# final_rev_no_smd.net
KiCad netlist of a schematic drawn in EAGLE
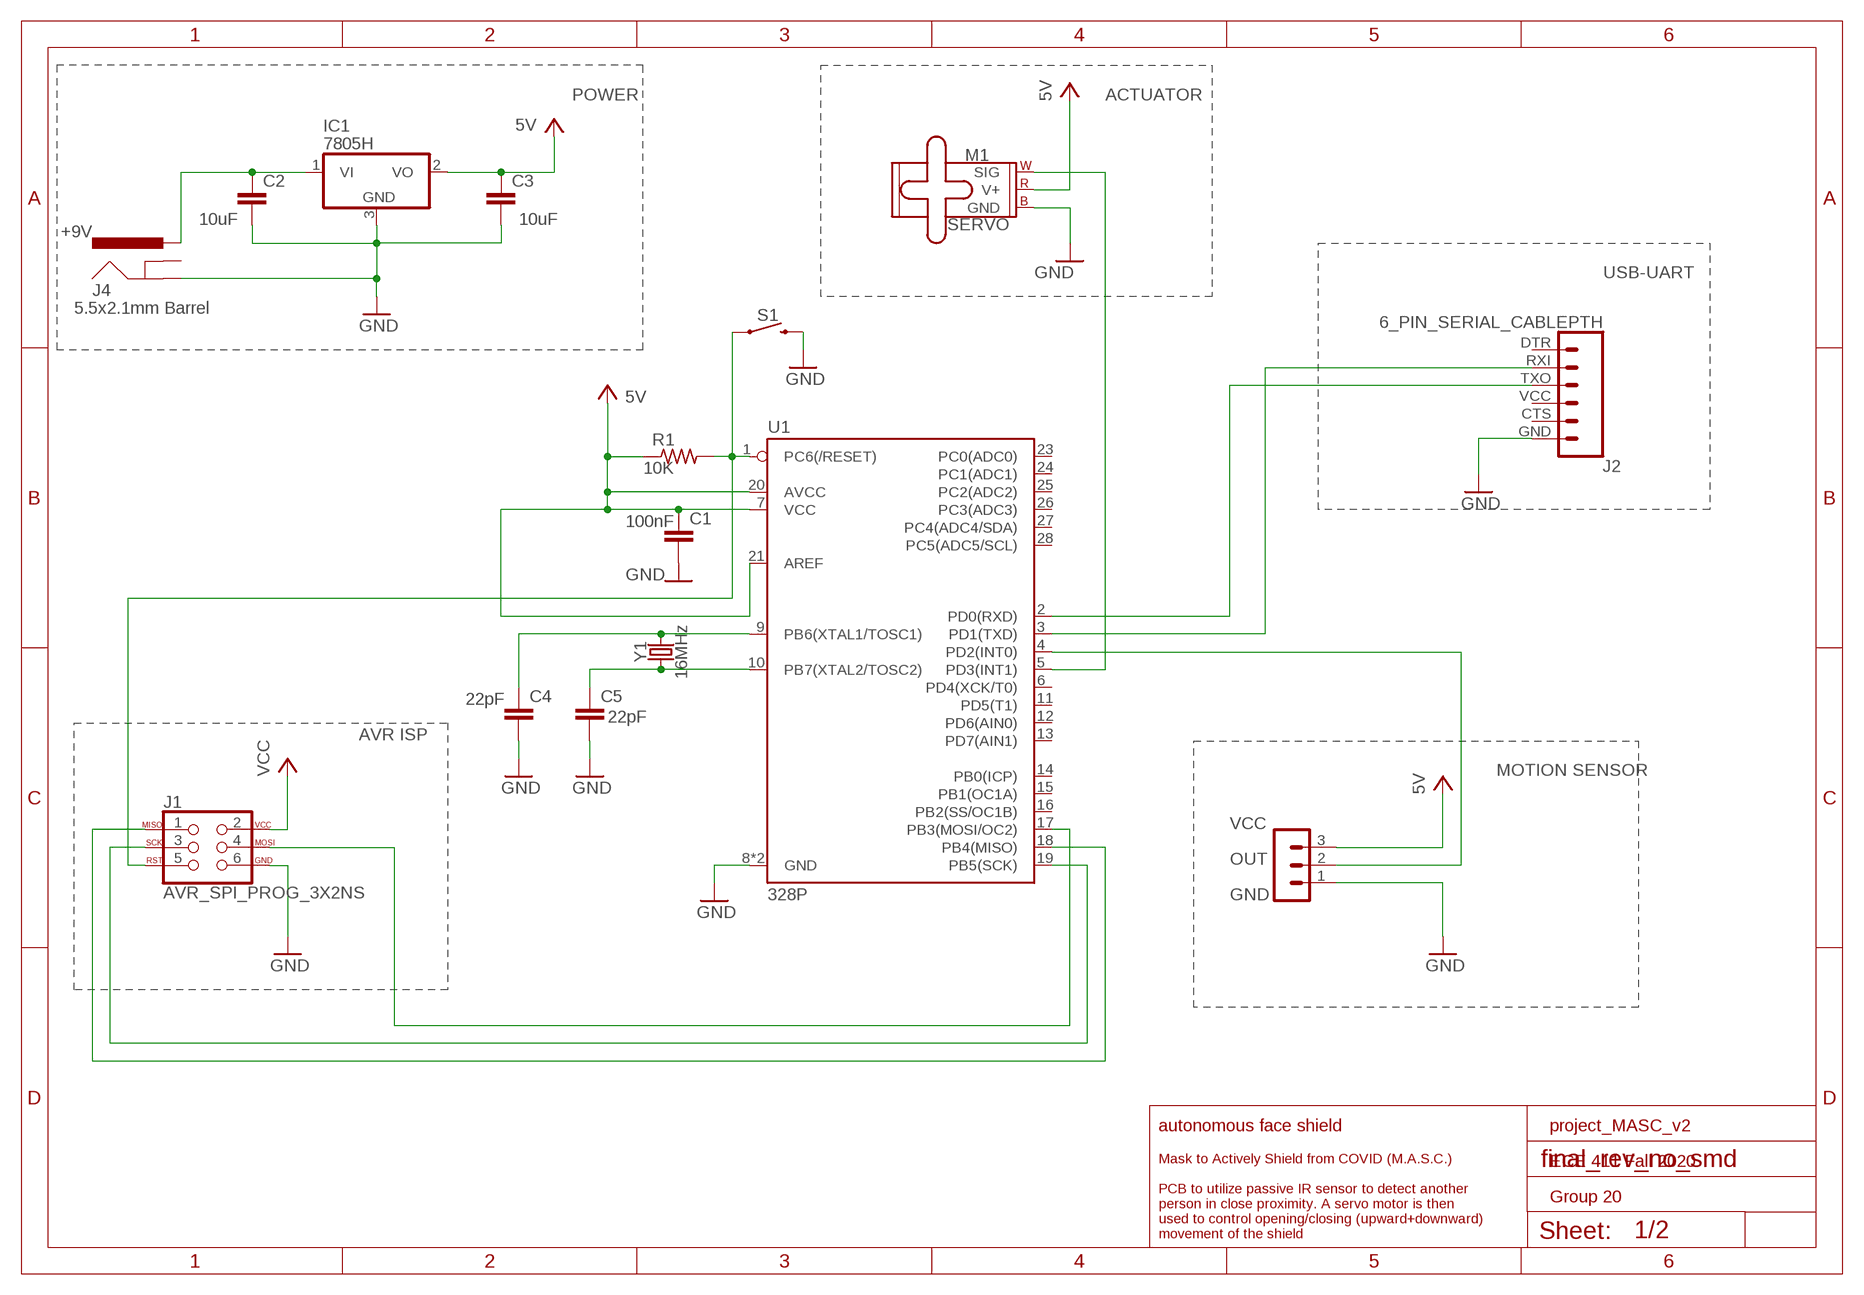
[diagram p0: schematic, sheet 1]

(export (version "E")
  (design (tool "Eeschema 10.0.6"))
  (components
    (comp (ref "C1")
      (value "C2.5/2")
      (footprint "eagle-import:C2.5-2")
      (libsource (lib "eagle-import") (part "C2.5/2"))
    )
    (comp (ref "C2")
      (value "C2.5/2")
      (footprint "eagle-import:C2.5-2")
      (libsource (lib "eagle-import") (part "C2.5/2"))
    )
    (comp (ref "C3")
      (value "C2.5/2")
      (footprint "eagle-import:C2.5-2")
      (libsource (lib "eagle-import") (part "C2.5/2"))
    )
    (comp (ref "C4")
      (value "C2.5/2")
      (footprint "eagle-import:C2.5-2")
      (libsource (lib "eagle-import") (part "C2.5/2"))
    )
    (comp (ref "C5")
      (value "C2.5/2")
      (footprint "eagle-import:C2.5-2")
      (libsource (lib "eagle-import") (part "C2.5/2"))
    )
    (comp (ref "IC1")
      (value "7805H")
      (footprint "eagle-import:TO39")
      (libsource (lib "eagle-import") (part "78H05"))
    )
    (comp (ref "J1")
      (value "AVR_SPI_PROG_3X2NS")
      (footprint "eagle-import:2X3-NS")
      (libsource (lib "eagle-import") (part "AVR_SPI_PROG_3X2NS"))
    )
    (comp (ref "J2")
      (value "6_PIN_SERIAL_CABLEPTH")
      (footprint "eagle-import:FTDI_BASIC")
      (libsource (lib "eagle-import") (part "6_PIN_SERIAL_CABLEPTH"))
    )
    (comp (ref "J4")
      (value "5.5x2.1mm Barrel")
      (footprint "eagle-import:POWER_JACK_SMD")
      (libsource (lib "eagle-import") (part "POWER_JACKSMD"))
    )
    (comp (ref "M1")
      (value "SERVO")
      (footprint "eagle-import:1X03")
      (libsource (lib "eagle-import") (part "SERVO"))
    )
    (comp (ref "R1")
      (value "R-US_0204/7")
      (footprint "eagle-import:0204_7")
      (libsource (lib "eagle-import") (part "R-US_0204/7"))
    )
    (comp (ref "S1")
      (value "MOMENTARY-SWITCH-SPST-PTH-6.0MM")
      (footprint "eagle-import:TACTILE_SWITCH_PTH_6.0MM")
      (libsource (lib "eagle-import") (part "MOMENTARY-SWITCH-SPST-PTH-6.0MM"))
    )
    (comp (ref "SV1")
      (value "MA03-1")
      (footprint "eagle-import:MA03-1")
      (libsource (lib "eagle-import") (part "MA03-1"))
    )
    (comp (ref "U1")
      (value "328P")
      (footprint "eagle-import:DIP28")
      (libsource (lib "eagle-import") (part "ATMEGA328P_PDIP"))
    )
    (comp (ref "Y1")
      (value "16MHz")
      (footprint "eagle-import:HC49US")
      (libsource (lib "eagle-import") (part "CRYSTAL-16MHZPTH-HC49US"))
    )
  )
  (nets
    (net (code "1") (name "GND") (class "Default")
      (node (ref "C1") (pin "2") (pinfunction "2_2") (pintype "passive"))
      (node (ref "C2") (pin "2") (pinfunction "2_2") (pintype "passive"))
      (node (ref "C3") (pin "2") (pinfunction "2_2") (pintype "passive"))
      (node (ref "C4") (pin "2") (pinfunction "2_2") (pintype "passive"))
      (node (ref "C5") (pin "2") (pinfunction "2_2") (pintype "passive"))
      (node (ref "IC1") (pin "3") (pinfunction "GND_3") (pintype "passive"))
      (node (ref "J1") (pin "6") (pinfunction "6_6") (pintype "passive"))
      (node (ref "J2") (pin "GND") (pinfunction "6_GND") (pintype "passive"))
      (node (ref "J4") (pin "P$4") (pinfunction "GND_P$4") (pintype "bidirectional"))
      (node (ref "M1") (pin "3") (pinfunction "GND_3") (pintype "bidirectional"))
      (node (ref "S1") (pin "3") (pinfunction "2_3") (pintype "passive"))
      (node (ref "SV1") (pin "1") (pinfunction "1_1") (pintype "passive"))
      (node (ref "U1") (pin "22") (pinfunction "GND_22") (pintype "bidirectional"))
      (node (ref "U1") (pin "8") (pinfunction "GND_8") (pintype "bidirectional"))
    )
    (net (code "2") (name "Net-(IC1-VI)") (class "Default")
      (node (ref "C2") (pin "1") (pinfunction "1_1") (pintype "passive"))
      (node (ref "IC1") (pin "1") (pinfunction "VI_1") (pintype "input"))
      (node (ref "J4") (pin "VIN0") (pinfunction "PWR_VIN0") (pintype "bidirectional"))
    )
    (net (code "3") (name "Net-(J2-2)") (class "Default")
      (node (ref "J2") (pin "RXI") (pinfunction "2_RXI") (pintype "passive"))
      (node (ref "U1") (pin "3") (pinfunction "PD1(TXD)_3") (pintype "bidirectional"))
    )
    (net (code "4") (name "Net-(J2-3)") (class "Default")
      (node (ref "J2") (pin "TXO") (pinfunction "3_TXO") (pintype "passive"))
      (node (ref "U1") (pin "2") (pinfunction "PD0(RXD)_2") (pintype "bidirectional"))
    )
    (net (code "5") (name "Net-(M1-SIG)") (class "Default")
      (node (ref "M1") (pin "1") (pinfunction "SIG_1") (pintype "bidirectional"))
      (node (ref "U1") (pin "5") (pinfunction "PD3(INT1)_5") (pintype "bidirectional"))
    )
    (net (code "6") (name "Net-(U1-PB3(MOSI{slash}OC2))") (class "Default")
      (node (ref "J1") (pin "4") (pinfunction "4_4") (pintype "passive"))
      (node (ref "U1") (pin "17") (pinfunction "PB3(MOSI/OC2)_17") (pintype "bidirectional"))
    )
    (net (code "7") (name "Net-(U1-PB4(MISO))") (class "Default")
      (node (ref "J1") (pin "1") (pinfunction "1_1") (pintype "passive"))
      (node (ref "U1") (pin "18") (pinfunction "PB4(MISO)_18") (pintype "bidirectional"))
    )
    (net (code "8") (name "Net-(U1-PB5(SCK))") (class "Default")
      (node (ref "J1") (pin "3") (pinfunction "3_3") (pintype "passive"))
      (node (ref "U1") (pin "19") (pinfunction "PB5(SCK)_19") (pintype "bidirectional"))
    )
    (net (code "9") (name "Net-(U1-PB6(XTAL1{slash}TOSC1))") (class "Default")
      (node (ref "C4") (pin "1") (pinfunction "1_1") (pintype "passive"))
      (node (ref "U1") (pin "9") (pinfunction "PB6(XTAL1/TOSC1)_9") (pintype "bidirectional"))
      (node (ref "Y1") (pin "2") (pinfunction "2_2") (pintype "passive"))
    )
    (net (code "10") (name "Net-(U1-PB7(XTAL2{slash}TOSC2))") (class "Default")
      (node (ref "C5") (pin "1") (pinfunction "1_1") (pintype "passive"))
      (node (ref "U1") (pin "10") (pinfunction "PB7(XTAL2/TOSC2)_10") (pintype "bidirectional"))
      (node (ref "Y1") (pin "1") (pinfunction "1_1") (pintype "passive"))
    )
    (net (code "11") (name "Net-(U1-PC6({slash}RESET))") (class "Default")
      (node (ref "J1") (pin "5") (pinfunction "5_5") (pintype "passive"))
      (node (ref "R1") (pin "2") (pinfunction "2_2") (pintype "passive"))
      (node (ref "S1") (pin "1") (pinfunction "1_1") (pintype "passive"))
      (node (ref "U1") (pin "1") (pinfunction "PC6(/RESET)_1") (pintype "bidirectional"))
    )
    (net (code "12") (name "Net-(U1-PD2(INT0))") (class "Default")
      (node (ref "SV1") (pin "2") (pinfunction "2_2") (pintype "passive"))
      (node (ref "U1") (pin "4") (pinfunction "PD2(INT0)_4") (pintype "bidirectional"))
    )
    (net (code "13") (name "VCC") (class "Default")
      (node (ref "C1") (pin "1") (pinfunction "1_1") (pintype "passive"))
      (node (ref "C3") (pin "1") (pinfunction "1_1") (pintype "passive"))
      (node (ref "IC1") (pin "2") (pinfunction "VO_2") (pintype "passive"))
      (node (ref "J1") (pin "2") (pinfunction "2_2") (pintype "passive"))
      (node (ref "M1") (pin "2") (pinfunction "V+_2") (pintype "bidirectional"))
      (node (ref "R1") (pin "1") (pinfunction "1_1") (pintype "passive"))
      (node (ref "SV1") (pin "3") (pinfunction "3_3") (pintype "passive"))
      (node (ref "U1") (pin "20") (pinfunction "AVCC_20") (pintype "bidirectional"))
      (node (ref "U1") (pin "21") (pinfunction "AREF_21") (pintype "bidirectional"))
      (node (ref "U1") (pin "7") (pinfunction "VCC_7") (pintype "bidirectional"))
    )
    (net (code "14") (name "unconnected-(J2-1-PadDTR)") (class "Default")
      (node (ref "J2") (pin "DTR") (pinfunction "1_DTR") (pintype "passive"))
    )
    (net (code "15") (name "unconnected-(J2-4-PadVCC)") (class "Default")
      (node (ref "J2") (pin "VCC") (pinfunction "4_VCC") (pintype "passive"))
    )
    (net (code "16") (name "unconnected-(J2-5-PadCTS)") (class "Default")
      (node (ref "J2") (pin "CTS") (pinfunction "5_CTS") (pintype "passive"))
    )
    (net (code "17") (name "unconnected-(J4-GNDBREAK-PadGND)") (class "Default")
      (node (ref "J4") (pin "GND") (pinfunction "GNDBREAK_GND") (pintype "bidirectional"))
    )
    (net (code "18") (name "unconnected-(U1-PB0(ICP)-Pad14)") (class "Default")
      (node (ref "U1") (pin "14") (pinfunction "PB0(ICP)_14") (pintype "bidirectional"))
    )
    (net (code "19") (name "unconnected-(U1-PB1(OC1A)-Pad15)") (class "Default")
      (node (ref "U1") (pin "15") (pinfunction "PB1(OC1A)_15") (pintype "bidirectional"))
    )
    (net (code "20") (name "unconnected-(U1-PB2(SS{slash}OC1B)-Pad16)") (class "Default")
      (node (ref "U1") (pin "16") (pinfunction "PB2(SS/OC1B)_16") (pintype "bidirectional"))
    )
    (net (code "21") (name "unconnected-(U1-PC0(ADC0)-Pad23)") (class "Default")
      (node (ref "U1") (pin "23") (pinfunction "PC0(ADC0)_23") (pintype "bidirectional"))
    )
    (net (code "22") (name "unconnected-(U1-PC1(ADC1)-Pad24)") (class "Default")
      (node (ref "U1") (pin "24") (pinfunction "PC1(ADC1)_24") (pintype "bidirectional"))
    )
    (net (code "23") (name "unconnected-(U1-PC2(ADC2)-Pad25)") (class "Default")
      (node (ref "U1") (pin "25") (pinfunction "PC2(ADC2)_25") (pintype "bidirectional"))
    )
    (net (code "24") (name "unconnected-(U1-PC3(ADC3)-Pad26)") (class "Default")
      (node (ref "U1") (pin "26") (pinfunction "PC3(ADC3)_26") (pintype "bidirectional"))
    )
    (net (code "25") (name "unconnected-(U1-PC4(ADC4{slash}SDA)-Pad27)") (class "Default")
      (node (ref "U1") (pin "27") (pinfunction "PC4(ADC4/SDA)_27") (pintype "bidirectional"))
    )
    (net (code "26") (name "unconnected-(U1-PC5(ADC5{slash}SCL)-Pad28)") (class "Default")
      (node (ref "U1") (pin "28") (pinfunction "PC5(ADC5/SCL)_28") (pintype "bidirectional"))
    )
    (net (code "27") (name "unconnected-(U1-PD4(XCK{slash}T0)-Pad6)") (class "Default")
      (node (ref "U1") (pin "6") (pinfunction "PD4(XCK/T0)_6") (pintype "bidirectional"))
    )
    (net (code "28") (name "unconnected-(U1-PD5(T1)-Pad11)") (class "Default")
      (node (ref "U1") (pin "11") (pinfunction "PD5(T1)_11") (pintype "bidirectional"))
    )
    (net (code "29") (name "unconnected-(U1-PD6(AIN0)-Pad12)") (class "Default")
      (node (ref "U1") (pin "12") (pinfunction "PD6(AIN0)_12") (pintype "bidirectional"))
    )
    (net (code "30") (name "unconnected-(U1-PD7(AIN1)-Pad13)") (class "Default")
      (node (ref "U1") (pin "13") (pinfunction "PD7(AIN1)_13") (pintype "bidirectional"))
    )
  )
)
